# power.net
KiCad netlist of a schematic drawn in Altium Designer
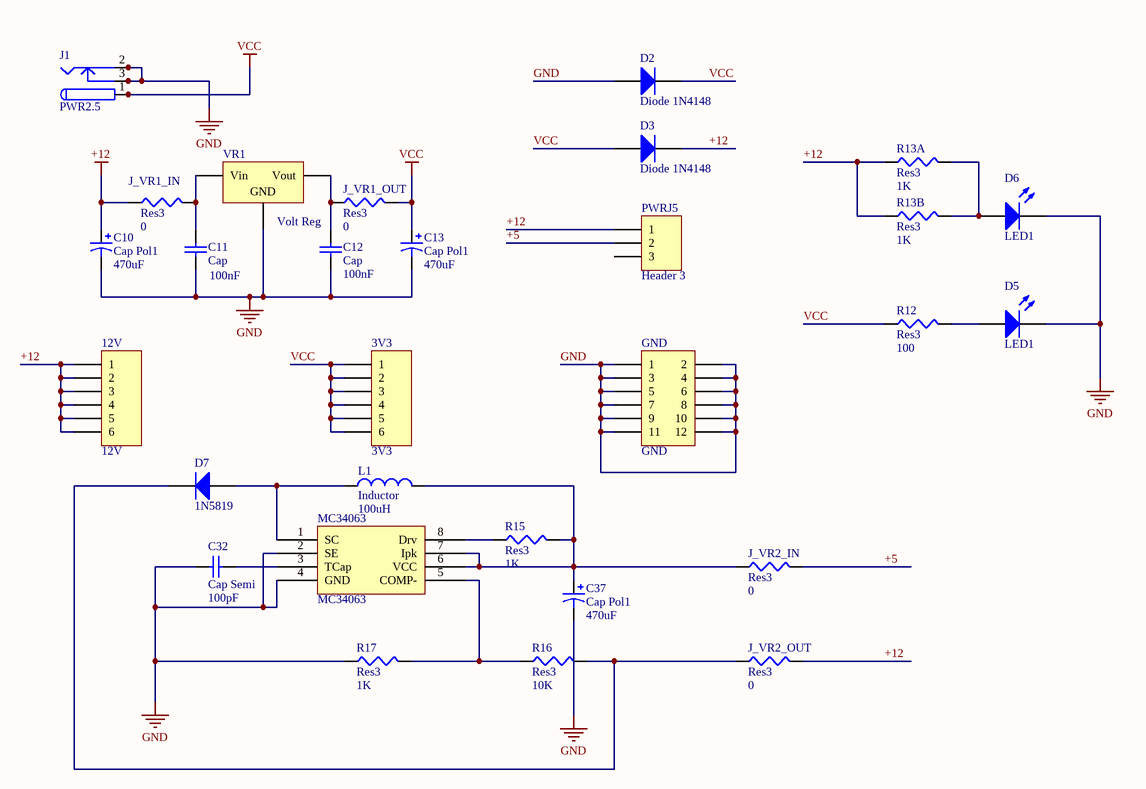
[diagram p0: power.SchDoc]

(export (version "E")
  (design (tool "Eeschema 10.0.6"))
  (components
    (comp (ref "3V3")
      (value "3V3")
      (footprint "HDR1X6")
      (description "Header, 6-Pin")
      (fields (field (name "PUBLISHER") "Altium Limited"))
      (libsource (lib "Miscellaneous Connectors") (part "Header 6"))
    )
    (comp (ref "12V")
      (value "12V")
      (footprint "HDR1X6")
      (description "Header, 6-Pin")
      (fields (field (name "PUBLISHER") "Altium Limited"))
      (libsource (lib "Miscellaneous Connectors") (part "Header 6"))
    )
    (comp (ref "C10")
      (value "Cap Pol1")
      (footprint "Cap8*14")
      (description "Polarized Capacitor (Radial)")
      (fields (field (name "ALTIUM_VALUE") "470uF") (field (name "PUBLISHER") "Altium Limited"))
      (libsource (lib "Miscellaneous Devices") (part "Cap Pol1"))
    )
    (comp (ref "C11")
      (value "Cap")
      (footprint "1608[0603]")
      (description "Capacitor")
      (fields (field (name "ALTIUM_VALUE") "100nF") (field (name "PUBLISHER") "Altium Limited"))
      (libsource (lib "Miscellaneous Devices") (part "Cap"))
    )
    (comp (ref "C12")
      (value "Cap")
      (footprint "1608[0603]")
      (description "Capacitor")
      (fields (field (name "ALTIUM_VALUE") "100nF") (field (name "PUBLISHER") "Altium Limited"))
      (libsource (lib "Miscellaneous Devices") (part "Cap"))
    )
    (comp (ref "C13")
      (value "Cap Pol1")
      (footprint "Cap8*14")
      (description "Polarized Capacitor (Radial)")
      (fields (field (name "ALTIUM_VALUE") "470uF") (field (name "PUBLISHER") "Altium Limited"))
      (libsource (lib "Miscellaneous Devices") (part "Cap Pol1"))
    )
    (comp (ref "C32")
      (value "Cap Semi")
      (footprint "1608[0603]")
      (description "Capacitor (Semiconductor SIM Model)")
      (fields (field (name "ALTIUM_VALUE") "100pF") (field (name "PUBLISHER") "Altium Limited"))
      (libsource (lib "Miscellaneous Devices") (part "Cap Semi"))
    )
    (comp (ref "C37")
      (value "Cap Pol1")
      (footprint "Cap8*14")
      (description "Polarized Capacitor (Radial)")
      (fields (field (name "ALTIUM_VALUE") "470uF") (field (name "PUBLISHER") "Altium Limited"))
      (libsource (lib "Miscellaneous Devices") (part "Cap Pol1"))
    )
    (comp (ref "D2")
      (value "Diode 1N4148")
      (footprint "DO-35")
      (description "High Conductance Fast Diode")
      (fields (field (name "PUBLISHER") "Altium Limited"))
      (libsource (lib "Miscellaneous Devices") (part "Diode 1N4148"))
    )
    (comp (ref "D3")
      (value "Diode 1N4148")
      (footprint "DO-35")
      (description "High Conductance Fast Diode")
      (fields (field (name "PUBLISHER") "Altium Limited"))
      (libsource (lib "Miscellaneous Devices") (part "Diode 1N4148"))
    )
    (comp (ref "D5")
      (value "LED1")
      (footprint "Cap5x10")
      (description "Typical RED GaAs LED")
      (fields (field (name "PUBLISHER") "Altium Limited"))
      (libsource (lib "Miscellaneous Devices") (part "LED1"))
    )
    (comp (ref "D6")
      (value "LED1")
      (footprint "Cap5x10")
      (description "Typical RED GaAs LED")
      (fields (field (name "PUBLISHER") "Altium Limited"))
      (libsource (lib "Miscellaneous Devices") (part "LED1"))
    )
    (comp (ref "D7")
      (value "1N5819")
      (footprint "425")
      (description "High Conductance Fast Diode")
      (fields (field (name "PUBLISHER") "Altium Limited"))
      (libsource (lib "Miscellaneous Devices") (part "Diode 1N4148"))
    )
    (comp (ref "GND")
      (value "GND")
      (footprint "HDR2X6")
      (description "Header, 6-Pin, Dual row")
      (fields (field (name "PUBLISHER") "Altium Limited"))
      (libsource (lib "Miscellaneous Connectors") (part "Header 6X2"))
    )
    (comp (ref "J1")
      (value "PWR2.5")
      (footprint "PCBComponent_1")
      (description "Low Voltage Power Supply Connector")
      (fields (field (name "PUBLISHER") "Altium Limited"))
      (libsource (lib "Miscellaneous Connectors") (part "PWR2.5"))
    )
    (comp (ref "J_VR1_IN")
      (value "Res3")
      (footprint "JUMPER2")
      (description "Resistor")
      (fields (field (name "ALTIUM_VALUE") "0") (field (name "PUBLISHER") "Altium Limited"))
      (libsource (lib "Miscellaneous Devices") (part "Res3"))
    )
    (comp (ref "J_VR1_OUT")
      (value "Res3")
      (footprint "JUMPER2")
      (description "Resistor")
      (fields (field (name "ALTIUM_VALUE") "0") (field (name "PUBLISHER") "Altium Limited"))
      (libsource (lib "Miscellaneous Devices") (part "Res3"))
    )
    (comp (ref "J_VR2_IN")
      (value "Res3")
      (footprint "JUMPER2")
      (description "Resistor")
      (fields (field (name "ALTIUM_VALUE") "0") (field (name "PUBLISHER") "Altium Limited"))
      (libsource (lib "Miscellaneous Devices") (part "Res3"))
    )
    (comp (ref "J_VR2_OUT")
      (value "Res3")
      (footprint "JUMPER2")
      (description "Resistor")
      (fields (field (name "ALTIUM_VALUE") "0") (field (name "PUBLISHER") "Altium Limited"))
      (libsource (lib "Miscellaneous Devices") (part "Res3"))
    )
    (comp (ref "L1")
      (value "Inductor")
      (footprint "Cap8*14")
      (fields (field (name "ALTIUM_VALUE") "100uH") (field (name "PUBLISHER") "Altium Limited"))
      (libsource (lib "Miscellaneous Devices") (part "Inductor"))
    )
    (comp (ref "MC34063")
      (value "MC34063")
      (footprint "MC34063")
      (libsource (lib "MC34063") (part "MC34063"))
    )
    (comp (ref "PWRJ5")
      (value "Header 3")
      (footprint "HDR1X3")
      (description "Header, 3-Pin")
      (fields (field (name "PUBLISHER") "Altium Limited"))
      (libsource (lib "Miscellaneous Connectors") (part "Header 3"))
    )
    (comp (ref "R12")
      (value "Res3")
      (footprint "J1-0603")
      (description "Resistor")
      (fields (field (name "ALTIUM_VALUE") "100") (field (name "PUBLISHER") "Altium Limited"))
      (libsource (lib "Miscellaneous Devices") (part "Res3"))
    )
    (comp (ref "R13A")
      (value "Res3")
      (footprint "J1-0603")
      (description "Resistor")
      (fields (field (name "ALTIUM_VALUE") "1K") (field (name "PUBLISHER") "Altium Limited"))
      (libsource (lib "Miscellaneous Devices") (part "Res3"))
    )
    (comp (ref "R13B")
      (value "Res3")
      (footprint "J1-0603")
      (description "Resistor")
      (fields (field (name "ALTIUM_VALUE") "1K") (field (name "PUBLISHER") "Altium Limited"))
      (libsource (lib "Miscellaneous Devices") (part "Res3"))
    )
    (comp (ref "R15")
      (value "Res3")
      (footprint "J1-0603")
      (description "Resistor")
      (fields (field (name "ALTIUM_VALUE") "1K") (field (name "PUBLISHER") "Altium Limited"))
      (libsource (lib "Miscellaneous Devices") (part "Res3"))
    )
    (comp (ref "R16")
      (value "Res3")
      (footprint "J1-0603")
      (description "Resistor")
      (fields (field (name "ALTIUM_VALUE") "10K") (field (name "PUBLISHER") "Altium Limited"))
      (libsource (lib "Miscellaneous Devices") (part "Res3"))
    )
    (comp (ref "R17")
      (value "Res3")
      (footprint "J1-0603")
      (description "Resistor")
      (fields (field (name "ALTIUM_VALUE") "1K") (field (name "PUBLISHER") "Altium Limited"))
      (libsource (lib "Miscellaneous Devices") (part "Res3"))
    )
    (comp (ref "VR1")
      (value "Volt Reg")
      (footprint "SOT223_L")
      (description "Voltage Regulator")
      (fields (field (name "PUBLISHER") "Altium Limited"))
      (libsource (lib "Miscellaneous Devices") (part "Volt Reg"))
    )
  )
  (nets
    (net (code "1") (name "+12") (class "Default")
      (node (ref "12V") (pin "1") (pinfunction "1_1") (pintype "passive"))
      (node (ref "12V") (pin "2") (pinfunction "2_2") (pintype "passive"))
      (node (ref "12V") (pin "3") (pinfunction "3_3") (pintype "passive"))
      (node (ref "12V") (pin "4") (pinfunction "4_4") (pintype "passive"))
      (node (ref "12V") (pin "5") (pinfunction "5_5") (pintype "passive"))
      (node (ref "12V") (pin "6") (pinfunction "6_6") (pintype "passive"))
      (node (ref "C10") (pin "1") (pinfunction "1_1") (pintype "passive"))
      (node (ref "D3") (pin "2") (pinfunction "K_2") (pintype "passive"))
      (node (ref "J_VR1_IN") (pin "1") (pinfunction "1_1") (pintype "passive"))
      (node (ref "J_VR2_OUT") (pin "2") (pinfunction "2_2") (pintype "passive"))
      (node (ref "PWRJ5") (pin "1") (pinfunction "1_1") (pintype "passive"))
      (node (ref "R13A") (pin "1") (pinfunction "1_1") (pintype "passive"))
      (node (ref "R13B") (pin "1") (pinfunction "1_1") (pintype "passive"))
    )
    (net (code "2") (name "/+5") (class "Default")
      (node (ref "J_VR2_IN") (pin "2") (pinfunction "2_2") (pintype "passive"))
      (node (ref "PWRJ5") (pin "2") (pinfunction "2_2") (pintype "passive"))
    )
    (net (code "3") (name "GND") (class "Default")
      (node (ref "C10") (pin "2") (pinfunction "2_2") (pintype "passive"))
      (node (ref "C11") (pin "1") (pinfunction "1_1") (pintype "passive"))
      (node (ref "C12") (pin "1") (pinfunction "1_1") (pintype "passive"))
      (node (ref "C13") (pin "2") (pinfunction "2_2") (pintype "passive"))
      (node (ref "C32") (pin "1") (pinfunction "1_1") (pintype "passive"))
      (node (ref "C37") (pin "2") (pinfunction "2_2") (pintype "passive"))
      (node (ref "D2") (pin "1") (pinfunction "A_1") (pintype "passive"))
      (node (ref "D5") (pin "2") (pinfunction "K_2") (pintype "passive"))
      (node (ref "D6") (pin "2") (pinfunction "K_2") (pintype "passive"))
      (node (ref "GND") (pin "1") (pinfunction "1_1") (pintype "passive"))
      (node (ref "GND") (pin "10") (pinfunction "10_10") (pintype "passive"))
      (node (ref "GND") (pin "11") (pinfunction "11_11") (pintype "passive"))
      (node (ref "GND") (pin "12") (pinfunction "12_12") (pintype "passive"))
      (node (ref "GND") (pin "2") (pinfunction "2_2") (pintype "passive"))
      (node (ref "GND") (pin "3") (pinfunction "3_3") (pintype "passive"))
      (node (ref "GND") (pin "4") (pinfunction "4_4") (pintype "passive"))
      (node (ref "GND") (pin "5") (pinfunction "5_5") (pintype "passive"))
      (node (ref "GND") (pin "6") (pinfunction "6_6") (pintype "passive"))
      (node (ref "GND") (pin "7") (pinfunction "7_7") (pintype "passive"))
      (node (ref "GND") (pin "8") (pinfunction "8_8") (pintype "passive"))
      (node (ref "GND") (pin "9") (pinfunction "9_9") (pintype "passive"))
      (node (ref "J1") (pin "2") (pinfunction "2_2") (pintype "power_in"))
      (node (ref "J1") (pin "2A") (pinfunction "2A_2A") (pintype "power_in"))
      (node (ref "J1") (pin "2B") (pinfunction "2B_2B") (pintype "power_in"))
      (node (ref "J1") (pin "3") (pinfunction "3_3") (pintype "power_in"))
      (node (ref "J1") (pin "3A") (pinfunction "3A_3A") (pintype "power_in"))
      (node (ref "J1") (pin "3B") (pinfunction "3B_3B") (pintype "power_in"))
      (node (ref "MC34063") (pin "2") (pinfunction "SE_2") (pintype "passive"))
      (node (ref "MC34063") (pin "4") (pinfunction "GND_4") (pintype "passive"))
      (node (ref "R17") (pin "1") (pinfunction "1_1") (pintype "passive"))
      (node (ref "VR1") (pin "2") (pinfunction "GND_2") (pintype "passive"))
    )
    (net (code "4") (name "Net-(D5-A)") (class "Default")
      (node (ref "D5") (pin "1") (pinfunction "A_1") (pintype "passive"))
      (node (ref "R12") (pin "2") (pinfunction "2_2") (pintype "passive"))
    )
    (net (code "5") (name "Net-(D6-A)") (class "Default")
      (node (ref "D6") (pin "1") (pinfunction "A_1") (pintype "passive"))
      (node (ref "R13A") (pin "2") (pinfunction "2_2") (pintype "passive"))
      (node (ref "R13B") (pin "2") (pinfunction "2_2") (pintype "passive"))
    )
    (net (code "6") (name "Net-(D7-A)") (class "Default")
      (node (ref "D7") (pin "1") (pinfunction "A_1") (pintype "passive"))
      (node (ref "L1") (pin "1") (pinfunction "1_1") (pintype "passive"))
      (node (ref "MC34063") (pin "1") (pinfunction "SC_1") (pintype "passive"))
    )
    (net (code "7") (name "Net-(D7-K)") (class "Default")
      (node (ref "D7") (pin "2") (pinfunction "K_2") (pintype "passive"))
      (node (ref "J_VR2_OUT") (pin "1") (pinfunction "1_1") (pintype "passive"))
      (node (ref "R16") (pin "2") (pinfunction "2_2") (pintype "passive"))
    )
    (net (code "8") (name "Net-(MC34063-COMP-)") (class "Default")
      (node (ref "MC34063") (pin "5") (pinfunction "COMP-_5") (pintype "passive"))
      (node (ref "R16") (pin "1") (pinfunction "1_1") (pintype "passive"))
      (node (ref "R17") (pin "2") (pinfunction "2_2") (pintype "passive"))
    )
    (net (code "9") (name "Net-(MC34063-Drv)") (class "Default")
      (node (ref "MC34063") (pin "8") (pinfunction "Drv_8") (pintype "passive"))
      (node (ref "R15") (pin "1") (pinfunction "1_1") (pintype "passive"))
    )
    (net (code "10") (name "Net-(MC34063-Ipk)") (class "Default")
      (node (ref "C37") (pin "1") (pinfunction "1_1") (pintype "passive"))
      (node (ref "J_VR2_IN") (pin "1") (pinfunction "1_1") (pintype "passive"))
      (node (ref "L1") (pin "2") (pinfunction "2_2") (pintype "passive"))
      (node (ref "MC34063") (pin "6") (pinfunction "VCC_6") (pintype "passive"))
      (node (ref "MC34063") (pin "7") (pinfunction "Ipk_7") (pintype "passive"))
      (node (ref "R15") (pin "2") (pinfunction "2_2") (pintype "passive"))
    )
    (net (code "11") (name "Net-(MC34063-TCap)") (class "Default")
      (node (ref "C32") (pin "2") (pinfunction "2_2") (pintype "passive"))
      (node (ref "MC34063") (pin "3") (pinfunction "TCap_3") (pintype "passive"))
    )
    (net (code "12") (name "Net-(VR1-Vin)") (class "Default")
      (node (ref "C11") (pin "2") (pinfunction "2_2") (pintype "passive"))
      (node (ref "J_VR1_IN") (pin "2") (pinfunction "2_2") (pintype "passive"))
      (node (ref "VR1") (pin "1") (pinfunction "Vin_1") (pintype "passive"))
    )
    (net (code "13") (name "Net-(VR1-Vout)") (class "Default")
      (node (ref "C12") (pin "2") (pinfunction "2_2") (pintype "passive"))
      (node (ref "J_VR1_OUT") (pin "1") (pinfunction "1_1") (pintype "passive"))
      (node (ref "VR1") (pin "3") (pinfunction "Vout_3") (pintype "passive"))
    )
    (net (code "14") (name "VCC") (class "Default")
      (node (ref "3V3") (pin "1") (pinfunction "1_1") (pintype "passive"))
      (node (ref "3V3") (pin "2") (pinfunction "2_2") (pintype "passive"))
      (node (ref "3V3") (pin "3") (pinfunction "3_3") (pintype "passive"))
      (node (ref "3V3") (pin "4") (pinfunction "4_4") (pintype "passive"))
      (node (ref "3V3") (pin "5") (pinfunction "5_5") (pintype "passive"))
      (node (ref "3V3") (pin "6") (pinfunction "6_6") (pintype "passive"))
      (node (ref "C13") (pin "1") (pinfunction "1_1") (pintype "passive"))
      (node (ref "D2") (pin "2") (pinfunction "K_2") (pintype "passive"))
      (node (ref "D3") (pin "1") (pinfunction "A_1") (pintype "passive"))
      (node (ref "J1") (pin "1") (pinfunction "1_1") (pintype "power_in"))
      (node (ref "J1") (pin "1A") (pinfunction "1A_1A") (pintype "power_in"))
      (node (ref "J1") (pin "1B") (pinfunction "1B_1B") (pintype "power_in"))
      (node (ref "J_VR1_OUT") (pin "2") (pinfunction "2_2") (pintype "passive"))
      (node (ref "R12") (pin "1") (pinfunction "1_1") (pintype "passive"))
    )
    (net (code "15") (name "unconnected-(PWRJ5-Pad3)") (class "Default")
      (node (ref "PWRJ5") (pin "3") (pinfunction "3_3") (pintype "passive"))
    )
  )
)
